# esp-prog-SMD.net
KiCad netlist of a schematic drawn in EAGLE
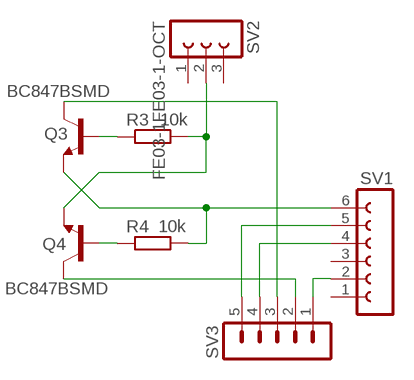
[diagram p0: schematic, sheet 1]

(export (version "E")
  (design (tool "Eeschema 10.0.6"))
  (components
    (comp (ref "Q3")
      (value "BC847BSMD")
      (footprint "eagle-import:SOT23")
      (libsource (lib "eagle-import") (part "BC847SMDB"))
    )
    (comp (ref "Q4")
      (value "BC847BSMD")
      (footprint "eagle-import:SOT23")
      (libsource (lib "eagle-import") (part "BC847SMDB"))
    )
    (comp (ref "R3")
      (value "10k")
      (footprint "eagle-import:R1206")
      (libsource (lib "eagle-import") (part "R-EU_R1206"))
    )
    (comp (ref "R4")
      (value "10k")
      (footprint "eagle-import:R1206")
      (libsource (lib "eagle-import") (part "R-EU_R1206"))
    )
    (comp (ref "SV1")
      (value "FE06-1")
      (footprint "eagle-import:FE06")
      (libsource (lib "eagle-import") (part "FE06-1"))
    )
    (comp (ref "SV2")
      (value "FE03-1FE03-1-OCT")
      (footprint "eagle-import:FE03-1-OCT")
      (libsource (lib "eagle-import") (part "FE03-1FE03-1-OCT"))
    )
    (comp (ref "SV3")
      (value "MA05-1")
      (footprint "eagle-import:MA05-1")
      (libsource (lib "eagle-import") (part "MA05-1"))
    )
  )
  (nets
    (net (code "1") (name "Net-(Q3-B)") (class "Default")
      (node (ref "Q3") (pin "1") (pinfunction "B_1") (pintype "passive"))
      (node (ref "R3") (pin "1") (pinfunction "1_1") (pintype "passive"))
    )
    (net (code "2") (name "Net-(Q3-C)") (class "Default")
      (node (ref "Q3") (pin "3") (pinfunction "C_3") (pintype "passive"))
      (node (ref "SV3") (pin "3") (pinfunction "3_3") (pintype "passive"))
    )
    (net (code "3") (name "Net-(Q3-E)") (class "Default")
      (node (ref "Q3") (pin "2") (pinfunction "E_2") (pintype "passive"))
      (node (ref "R4") (pin "2") (pinfunction "2_2") (pintype "passive"))
      (node (ref "SV1") (pin "6") (pinfunction "6_6") (pintype "passive"))
    )
    (net (code "4") (name "Net-(Q4-B)") (class "Default")
      (node (ref "Q4") (pin "1") (pinfunction "B_1") (pintype "passive"))
      (node (ref "R4") (pin "1") (pinfunction "1_1") (pintype "passive"))
    )
    (net (code "5") (name "Net-(Q4-C)") (class "Default")
      (node (ref "Q4") (pin "3") (pinfunction "C_3") (pintype "passive"))
      (node (ref "SV3") (pin "2") (pinfunction "2_2") (pintype "passive"))
    )
    (net (code "6") (name "Net-(Q4-E)") (class "Default")
      (node (ref "Q4") (pin "2") (pinfunction "E_2") (pintype "passive"))
      (node (ref "R3") (pin "2") (pinfunction "2_2") (pintype "passive"))
      (node (ref "SV2") (pin "2") (pinfunction "2_2") (pintype "passive"))
    )
    (net (code "7") (name "Net-(SV1-Pad2)") (class "Default")
      (node (ref "SV1") (pin "2") (pinfunction "2_2") (pintype "passive"))
      (node (ref "SV3") (pin "1") (pinfunction "1_1") (pintype "passive"))
    )
    (net (code "8") (name "Net-(SV1-Pad4)") (class "Default")
      (node (ref "SV1") (pin "4") (pinfunction "4_4") (pintype "passive"))
      (node (ref "SV3") (pin "4") (pinfunction "4_4") (pintype "passive"))
    )
    (net (code "9") (name "Net-(SV1-Pad5)") (class "Default")
      (node (ref "SV1") (pin "5") (pinfunction "5_5") (pintype "passive"))
      (node (ref "SV3") (pin "5") (pinfunction "5_5") (pintype "passive"))
    )
    (net (code "10") (name "unconnected-(SV1-Pad1)") (class "Default")
      (node (ref "SV1") (pin "1") (pinfunction "1_1") (pintype "passive"))
    )
    (net (code "11") (name "unconnected-(SV1-Pad3)") (class "Default")
      (node (ref "SV1") (pin "3") (pinfunction "3_3") (pintype "passive"))
    )
    (net (code "12") (name "unconnected-(SV2-Pad1)") (class "Default")
      (node (ref "SV2") (pin "1") (pinfunction "1_1") (pintype "passive"))
    )
    (net (code "13") (name "unconnected-(SV2-Pad3)") (class "Default")
      (node (ref "SV2") (pin "3") (pinfunction "3_3") (pintype "passive"))
    )
  )
)
